# cert3d_rev2.net
KiCad netlist of a schematic drawn in EAGLE
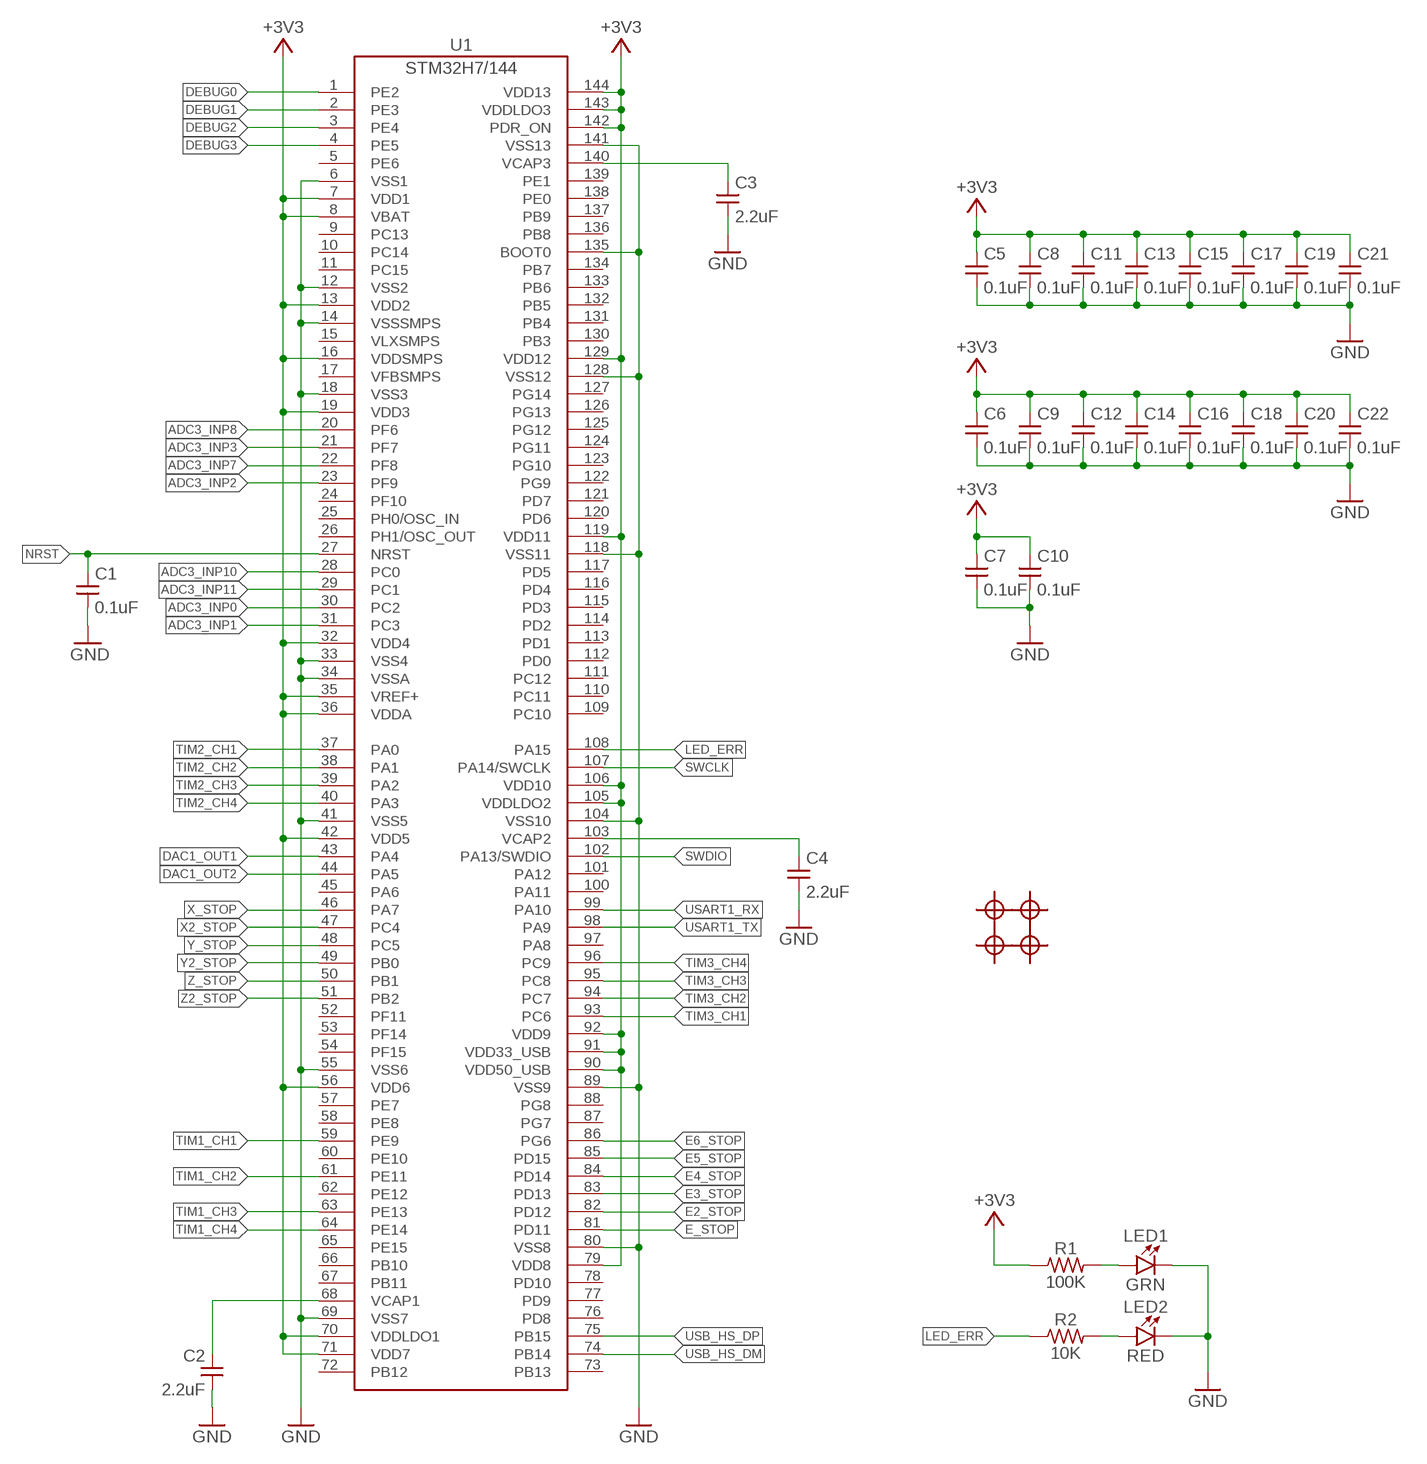
[diagram p0: schematic, sheet 1, part 1 of 2]
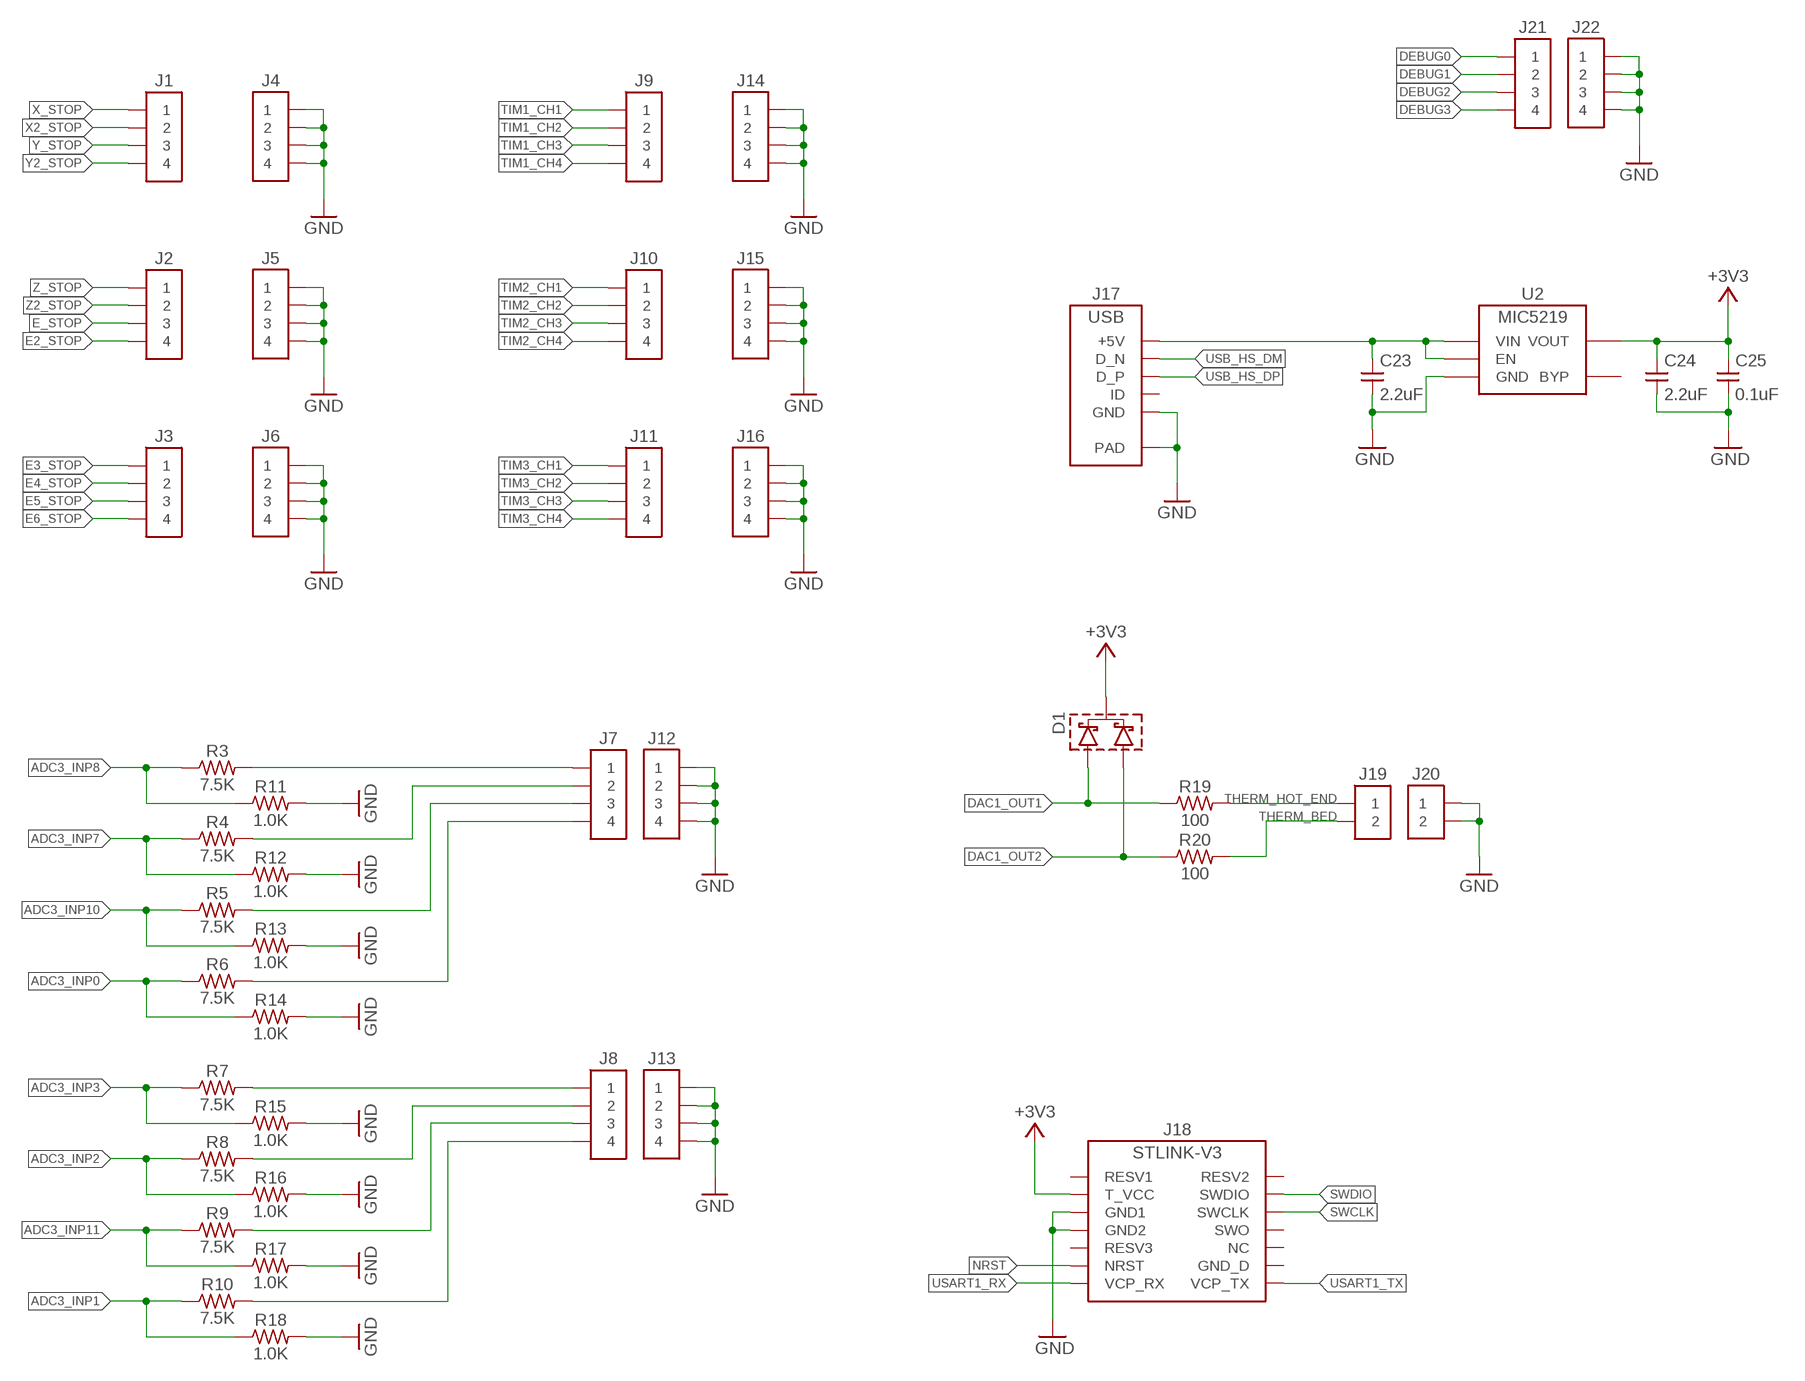
[diagram p1: schematic, sheet 1, part 2 of 2]

(export (version "E")
  (design (tool "Eeschema 10.0.6"))
  (components
    (comp (ref "C1")
      (value "0.1uF")
      (footprint "eagle-import:C0805-5MIL")
      (libsource (lib "eagle-import") (part "C_USC0805-5MIL"))
    )
    (comp (ref "C2")
      (value "2.2uF")
      (footprint "eagle-import:C0805-5MIL")
      (libsource (lib "eagle-import") (part "C_USC0805-5MIL"))
    )
    (comp (ref "C3")
      (value "2.2uF")
      (footprint "eagle-import:C0805-5MIL")
      (libsource (lib "eagle-import") (part "C_USC0805-5MIL"))
    )
    (comp (ref "C4")
      (value "2.2uF")
      (footprint "eagle-import:C0805-5MIL")
      (libsource (lib "eagle-import") (part "C_USC0805-5MIL"))
    )
    (comp (ref "C5")
      (value "0.1uF")
      (footprint "eagle-import:C0805-5MIL")
      (libsource (lib "eagle-import") (part "C_USC0805-5MIL"))
    )
    (comp (ref "C6")
      (value "0.1uF")
      (footprint "eagle-import:C0805-5MIL")
      (libsource (lib "eagle-import") (part "C_USC0805-5MIL"))
    )
    (comp (ref "C7")
      (value "0.1uF")
      (footprint "eagle-import:C0805-5MIL")
      (libsource (lib "eagle-import") (part "C_USC0805-5MIL"))
    )
    (comp (ref "C8")
      (value "0.1uF")
      (footprint "eagle-import:C0805-5MIL")
      (libsource (lib "eagle-import") (part "C_USC0805-5MIL"))
    )
    (comp (ref "C9")
      (value "0.1uF")
      (footprint "eagle-import:C0805-5MIL")
      (libsource (lib "eagle-import") (part "C_USC0805-5MIL"))
    )
    (comp (ref "C10")
      (value "0.1uF")
      (footprint "eagle-import:C0805-5MIL")
      (libsource (lib "eagle-import") (part "C_USC0805-5MIL"))
    )
    (comp (ref "C11")
      (value "0.1uF")
      (footprint "eagle-import:C0805-5MIL")
      (libsource (lib "eagle-import") (part "C_USC0805-5MIL"))
    )
    (comp (ref "C12")
      (value "0.1uF")
      (footprint "eagle-import:C0805-5MIL")
      (libsource (lib "eagle-import") (part "C_USC0805-5MIL"))
    )
    (comp (ref "C13")
      (value "0.1uF")
      (footprint "eagle-import:C0805-5MIL")
      (libsource (lib "eagle-import") (part "C_USC0805-5MIL"))
    )
    (comp (ref "C14")
      (value "0.1uF")
      (footprint "eagle-import:C0805-5MIL")
      (libsource (lib "eagle-import") (part "C_USC0805-5MIL"))
    )
    (comp (ref "C15")
      (value "0.1uF")
      (footprint "eagle-import:C0805-5MIL")
      (libsource (lib "eagle-import") (part "C_USC0805-5MIL"))
    )
    (comp (ref "C16")
      (value "0.1uF")
      (footprint "eagle-import:C0805-5MIL")
      (libsource (lib "eagle-import") (part "C_USC0805-5MIL"))
    )
    (comp (ref "C17")
      (value "0.1uF")
      (footprint "eagle-import:C0805-5MIL")
      (libsource (lib "eagle-import") (part "C_USC0805-5MIL"))
    )
    (comp (ref "C18")
      (value "0.1uF")
      (footprint "eagle-import:C0805-5MIL")
      (libsource (lib "eagle-import") (part "C_USC0805-5MIL"))
    )
    (comp (ref "C19")
      (value "0.1uF")
      (footprint "eagle-import:C0805-5MIL")
      (libsource (lib "eagle-import") (part "C_USC0805-5MIL"))
    )
    (comp (ref "C20")
      (value "0.1uF")
      (footprint "eagle-import:C0805-5MIL")
      (libsource (lib "eagle-import") (part "C_USC0805-5MIL"))
    )
    (comp (ref "C21")
      (value "0.1uF")
      (footprint "eagle-import:C0805-5MIL")
      (libsource (lib "eagle-import") (part "C_USC0805-5MIL"))
    )
    (comp (ref "C22")
      (value "0.1uF")
      (footprint "eagle-import:C0805-5MIL")
      (libsource (lib "eagle-import") (part "C_USC0805-5MIL"))
    )
    (comp (ref "C23")
      (value "2.2uF")
      (footprint "eagle-import:C0805-5MIL")
      (libsource (lib "eagle-import") (part "C_USC0805-5MIL"))
    )
    (comp (ref "C24")
      (value "2.2uF")
      (footprint "eagle-import:C0805-5MIL")
      (libsource (lib "eagle-import") (part "C_USC0805-5MIL"))
    )
    (comp (ref "C25")
      (value "0.1uF")
      (footprint "eagle-import:C0805-5MIL")
      (libsource (lib "eagle-import") (part "C_USC0805-5MIL"))
    )
    (comp (ref "D1")
      (value "SCHOTTKY_DUAL_CCBAT54C")
      (footprint "eagle-import:SOT23-3")
      (libsource (lib "eagle-import") (part "SCHOTTKY_DUAL_CCBAT54C"))
    )
    (comp (ref "FD1")
      (value "FIDUCIAL")
      (footprint "eagle-import:FID1MM")
      (libsource (lib "eagle-import") (part "FIDUCIAL"))
    )
    (comp (ref "FD2")
      (value "FIDUCIAL")
      (footprint "eagle-import:FID1MM")
      (libsource (lib "eagle-import") (part "FIDUCIAL"))
    )
    (comp (ref "FD3")
      (value "FIDUCIAL")
      (footprint "eagle-import:FID1MM")
      (libsource (lib "eagle-import") (part "FIDUCIAL"))
    )
    (comp (ref "FD4")
      (value "FIDUCIAL")
      (footprint "eagle-import:FID1MM")
      (libsource (lib "eagle-import") (part "FIDUCIAL"))
    )
    (comp (ref "J1")
      (value "CONN4TSW-S")
      (footprint "eagle-import:SAM-TSW-104-XX-X-S")
      (libsource (lib "eagle-import") (part "CONN4TSW-S"))
    )
    (comp (ref "J2")
      (value "CONN4TSW-S")
      (footprint "eagle-import:SAM-TSW-104-XX-X-S")
      (libsource (lib "eagle-import") (part "CONN4TSW-S"))
    )
    (comp (ref "J3")
      (value "CONN4TSW-S")
      (footprint "eagle-import:SAM-TSW-104-XX-X-S")
      (libsource (lib "eagle-import") (part "CONN4TSW-S"))
    )
    (comp (ref "J4")
      (value "CONN4TSW-S")
      (footprint "eagle-import:SAM-TSW-104-XX-X-S")
      (libsource (lib "eagle-import") (part "CONN4TSW-S"))
    )
    (comp (ref "J5")
      (value "CONN4TSW-S")
      (footprint "eagle-import:SAM-TSW-104-XX-X-S")
      (libsource (lib "eagle-import") (part "CONN4TSW-S"))
    )
    (comp (ref "J6")
      (value "CONN4TSW-S")
      (footprint "eagle-import:SAM-TSW-104-XX-X-S")
      (libsource (lib "eagle-import") (part "CONN4TSW-S"))
    )
    (comp (ref "J7")
      (value "CONN4TSW-S")
      (footprint "eagle-import:SAM-TSW-104-XX-X-S")
      (libsource (lib "eagle-import") (part "CONN4TSW-S"))
    )
    (comp (ref "J8")
      (value "CONN4TSW-S")
      (footprint "eagle-import:SAM-TSW-104-XX-X-S")
      (libsource (lib "eagle-import") (part "CONN4TSW-S"))
    )
    (comp (ref "J9")
      (value "CONN4TSW-S")
      (footprint "eagle-import:SAM-TSW-104-XX-X-S")
      (libsource (lib "eagle-import") (part "CONN4TSW-S"))
    )
    (comp (ref "J10")
      (value "CONN4TSW-S")
      (footprint "eagle-import:SAM-TSW-104-XX-X-S")
      (libsource (lib "eagle-import") (part "CONN4TSW-S"))
    )
    (comp (ref "J11")
      (value "CONN4TSW-S")
      (footprint "eagle-import:SAM-TSW-104-XX-X-S")
      (libsource (lib "eagle-import") (part "CONN4TSW-S"))
    )
    (comp (ref "J12")
      (value "CONN4TSW-S")
      (footprint "eagle-import:SAM-TSW-104-XX-X-S")
      (libsource (lib "eagle-import") (part "CONN4TSW-S"))
    )
    (comp (ref "J13")
      (value "CONN4TSW-S")
      (footprint "eagle-import:SAM-TSW-104-XX-X-S")
      (libsource (lib "eagle-import") (part "CONN4TSW-S"))
    )
    (comp (ref "J14")
      (value "CONN4TSW-S")
      (footprint "eagle-import:SAM-TSW-104-XX-X-S")
      (libsource (lib "eagle-import") (part "CONN4TSW-S"))
    )
    (comp (ref "J15")
      (value "CONN4TSW-S")
      (footprint "eagle-import:SAM-TSW-104-XX-X-S")
      (libsource (lib "eagle-import") (part "CONN4TSW-S"))
    )
    (comp (ref "J16")
      (value "CONN4TSW-S")
      (footprint "eagle-import:SAM-TSW-104-XX-X-S")
      (libsource (lib "eagle-import") (part "CONN4TSW-S"))
    )
    (comp (ref "J17")
      (value "USB-5PINTOPVIA")
      (footprint "eagle-import:HIR-ZX62R-B-5P-VIAS")
      (libsource (lib "eagle-import") (part "USB-5PINTOPVIA"))
    )
    (comp (ref "J18")
      (value "STLINK-V3/SWDCNC-3220")
      (footprint "eagle-import:CNC-3220-14-0100-00")
      (libsource (lib "eagle-import") (part "STLINK-V3/SWDCNC-3220"))
    )
    (comp (ref "J19")
      (value "CONN2TSW-S")
      (footprint "eagle-import:SAM-TSW-102-XX-X-S")
      (libsource (lib "eagle-import") (part "CONN2TSW-S"))
    )
    (comp (ref "J20")
      (value "CONN2TSW-S")
      (footprint "eagle-import:SAM-TSW-102-XX-X-S")
      (libsource (lib "eagle-import") (part "CONN2TSW-S"))
    )
    (comp (ref "J21")
      (value "CONN4TSW-S")
      (footprint "eagle-import:SAM-TSW-104-XX-X-S")
      (libsource (lib "eagle-import") (part "CONN4TSW-S"))
    )
    (comp (ref "J22")
      (value "CONN4TSW-S")
      (footprint "eagle-import:SAM-TSW-104-XX-X-S")
      (libsource (lib "eagle-import") (part "CONN4TSW-S"))
    )
    (comp (ref "LED1")
      (value "GRN")
      (footprint "eagle-import:CHIPLED0805-SMALL")
      (libsource (lib "eagle-import") (part "LEDCHIPLED0805-SMALL"))
    )
    (comp (ref "LED2")
      (value "RED")
      (footprint "eagle-import:CHIPLED0805-SMALL")
      (libsource (lib "eagle-import") (part "LEDCHIPLED0805-SMALL"))
    )
    (comp (ref "R1")
      (value "100K")
      (footprint "eagle-import:RES0805R-5MIL")
      (libsource (lib "eagle-import") (part "R_USRES0805-5MIL"))
    )
    (comp (ref "R2")
      (value "10K")
      (footprint "eagle-import:RES0805R-5MIL")
      (libsource (lib "eagle-import") (part "R_USRES0805-5MIL"))
    )
    (comp (ref "R3")
      (value "7.5K")
      (footprint "eagle-import:RES0805R-5MIL")
      (libsource (lib "eagle-import") (part "R_USRES0805-5MIL"))
    )
    (comp (ref "R4")
      (value "7.5K")
      (footprint "eagle-import:RES0805R-5MIL")
      (libsource (lib "eagle-import") (part "R_USRES0805-5MIL"))
    )
    (comp (ref "R5")
      (value "7.5K")
      (footprint "eagle-import:RES0805R-5MIL")
      (libsource (lib "eagle-import") (part "R_USRES0805-5MIL"))
    )
    (comp (ref "R6")
      (value "7.5K")
      (footprint "eagle-import:RES0805R-5MIL")
      (libsource (lib "eagle-import") (part "R_USRES0805-5MIL"))
    )
    (comp (ref "R7")
      (value "7.5K")
      (footprint "eagle-import:RES0805R-5MIL")
      (libsource (lib "eagle-import") (part "R_USRES0805-5MIL"))
    )
    (comp (ref "R8")
      (value "7.5K")
      (footprint "eagle-import:RES0805R-5MIL")
      (libsource (lib "eagle-import") (part "R_USRES0805-5MIL"))
    )
    (comp (ref "R9")
      (value "7.5K")
      (footprint "eagle-import:RES0805R-5MIL")
      (libsource (lib "eagle-import") (part "R_USRES0805-5MIL"))
    )
    (comp (ref "R10")
      (value "7.5K")
      (footprint "eagle-import:RES0805R-5MIL")
      (libsource (lib "eagle-import") (part "R_USRES0805-5MIL"))
    )
    (comp (ref "R11")
      (value "1.0K")
      (footprint "eagle-import:RES0805R-5MIL")
      (libsource (lib "eagle-import") (part "R_USRES0805-5MIL"))
    )
    (comp (ref "R12")
      (value "1.0K")
      (footprint "eagle-import:RES0805R-5MIL")
      (libsource (lib "eagle-import") (part "R_USRES0805-5MIL"))
    )
    (comp (ref "R13")
      (value "1.0K")
      (footprint "eagle-import:RES0805R-5MIL")
      (libsource (lib "eagle-import") (part "R_USRES0805-5MIL"))
    )
    (comp (ref "R14")
      (value "1.0K")
      (footprint "eagle-import:RES0805R-5MIL")
      (libsource (lib "eagle-import") (part "R_USRES0805-5MIL"))
    )
    (comp (ref "R15")
      (value "1.0K")
      (footprint "eagle-import:RES0805R-5MIL")
      (libsource (lib "eagle-import") (part "R_USRES0805-5MIL"))
    )
    (comp (ref "R16")
      (value "1.0K")
      (footprint "eagle-import:RES0805R-5MIL")
      (libsource (lib "eagle-import") (part "R_USRES0805-5MIL"))
    )
    (comp (ref "R17")
      (value "1.0K")
      (footprint "eagle-import:RES0805R-5MIL")
      (libsource (lib "eagle-import") (part "R_USRES0805-5MIL"))
    )
    (comp (ref "R18")
      (value "1.0K")
      (footprint "eagle-import:RES0805R-5MIL")
      (libsource (lib "eagle-import") (part "R_USRES0805-5MIL"))
    )
    (comp (ref "R19")
      (value "100")
      (footprint "eagle-import:RES0805R-5MIL")
      (libsource (lib "eagle-import") (part "R_USRES0805-5MIL"))
    )
    (comp (ref "R20")
      (value "100")
      (footprint "eagle-import:RES0805R-5MIL")
      (libsource (lib "eagle-import") (part "R_USRES0805-5MIL"))
    )
    (comp (ref "U1")
      (value "STM32H745-144")
      (footprint "eagle-import:LQFP144-20X20MM")
      (libsource (lib "eagle-import") (part "STM32H745-144"))
    )
    (comp (ref "U2")
      (value "MIC5219")
      (footprint "eagle-import:SOT23-5")
      (libsource (lib "eagle-import") (part "MIC5219"))
    )
  )
  (nets
    (net (code "1") (name "+3V3") (class "Default")
      (node (ref "C10") (pin "1") (pinfunction "1_1") (pintype "passive"))
      (node (ref "C11") (pin "1") (pinfunction "1_1") (pintype "passive"))
      (node (ref "C12") (pin "1") (pinfunction "1_1") (pintype "passive"))
      (node (ref "C13") (pin "1") (pinfunction "1_1") (pintype "passive"))
      (node (ref "C14") (pin "1") (pinfunction "1_1") (pintype "passive"))
      (node (ref "C15") (pin "1") (pinfunction "1_1") (pintype "passive"))
      (node (ref "C16") (pin "1") (pinfunction "1_1") (pintype "passive"))
      (node (ref "C17") (pin "1") (pinfunction "1_1") (pintype "passive"))
      (node (ref "C18") (pin "1") (pinfunction "1_1") (pintype "passive"))
      (node (ref "C19") (pin "1") (pinfunction "1_1") (pintype "passive"))
      (node (ref "C20") (pin "1") (pinfunction "1_1") (pintype "passive"))
      (node (ref "C21") (pin "1") (pinfunction "1_1") (pintype "passive"))
      (node (ref "C22") (pin "1") (pinfunction "1_1") (pintype "passive"))
      (node (ref "C24") (pin "1") (pinfunction "1_1") (pintype "passive"))
      (node (ref "C25") (pin "1") (pinfunction "1_1") (pintype "passive"))
      (node (ref "C5") (pin "1") (pinfunction "1_1") (pintype "passive"))
      (node (ref "C6") (pin "1") (pinfunction "1_1") (pintype "passive"))
      (node (ref "C7") (pin "1") (pinfunction "1_1") (pintype "passive"))
      (node (ref "C8") (pin "1") (pinfunction "1_1") (pintype "passive"))
      (node (ref "C9") (pin "1") (pinfunction "1_1") (pintype "passive"))
      (node (ref "D1") (pin "3") (pinfunction "C_3") (pintype "passive"))
      (node (ref "J18") (pin "3") (pinfunction "T_VCC_3") (pintype "input"))
      (node (ref "R1") (pin "1") (pinfunction "1_1") (pintype "passive"))
      (node (ref "U1") (pin "105") (pinfunction "VDDLDO2_105") (pintype "bidirectional"))
      (node (ref "U1") (pin "106") (pinfunction "VDD10_106") (pintype "bidirectional"))
      (node (ref "U1") (pin "119") (pinfunction "VDD11_119") (pintype "bidirectional"))
      (node (ref "U1") (pin "129") (pinfunction "VDD12_129") (pintype "bidirectional"))
      (node (ref "U1") (pin "13") (pinfunction "VDD2_13") (pintype "bidirectional"))
      (node (ref "U1") (pin "142") (pinfunction "PDR_ON_142") (pintype "bidirectional"))
      (node (ref "U1") (pin "143") (pinfunction "VDDLDO3_143") (pintype "bidirectional"))
      (node (ref "U1") (pin "144") (pinfunction "VDD13_144") (pintype "bidirectional"))
      (node (ref "U1") (pin "16") (pinfunction "VDDSMPS_16") (pintype "bidirectional"))
      (node (ref "U1") (pin "19") (pinfunction "VDD3_19") (pintype "bidirectional"))
      (node (ref "U1") (pin "32") (pinfunction "VDD4_32") (pintype "bidirectional"))
      (node (ref "U1") (pin "35") (pinfunction "VREF+_35") (pintype "bidirectional"))
      (node (ref "U1") (pin "36") (pinfunction "VDDA_36") (pintype "bidirectional"))
      (node (ref "U1") (pin "42") (pinfunction "VDD5_42") (pintype "bidirectional"))
      (node (ref "U1") (pin "56") (pinfunction "VDD6_56") (pintype "bidirectional"))
      (node (ref "U1") (pin "7") (pinfunction "VDD1_7") (pintype "bidirectional"))
      (node (ref "U1") (pin "70") (pinfunction "VDDLDO1_70") (pintype "bidirectional"))
      (node (ref "U1") (pin "71") (pinfunction "VDD7_71") (pintype "bidirectional"))
      (node (ref "U1") (pin "79") (pinfunction "VDD8_79") (pintype "bidirectional"))
      (node (ref "U1") (pin "8") (pinfunction "VBAT_8") (pintype "bidirectional"))
      (node (ref "U1") (pin "90") (pinfunction "VDD50_USB_90") (pintype "bidirectional"))
      (node (ref "U1") (pin "91") (pinfunction "VDD33_USB_91") (pintype "bidirectional"))
      (node (ref "U1") (pin "92") (pinfunction "VDD9_92") (pintype "bidirectional"))
      (node (ref "U2") (pin "5") (pinfunction "VOUT_5") (pintype "bidirectional"))
    )
    (net (code "2") (name "/THERM_BED") (class "Default")
      (node (ref "J19") (pin "2") (pinfunction "2_2") (pintype "passive"))
      (node (ref "R20") (pin "2") (pinfunction "2_2") (pintype "passive"))
    )
    (net (code "3") (name "/THERM_HOT_END") (class "Default")
      (node (ref "J19") (pin "1") (pinfunction "1_1") (pintype "passive"))
      (node (ref "R19") (pin "2") (pinfunction "2_2") (pintype "passive"))
    )
    (net (code "4") (name "ADC3_INP0") (class "Default")
      (node (ref "R14") (pin "1") (pinfunction "1_1") (pintype "passive"))
      (node (ref "R6") (pin "1") (pinfunction "1_1") (pintype "passive"))
      (node (ref "U1") (pin "30") (pinfunction "PC2_30") (pintype "bidirectional"))
    )
    (net (code "5") (name "ADC3_INP1") (class "Default")
      (node (ref "R10") (pin "1") (pinfunction "1_1") (pintype "passive"))
      (node (ref "R18") (pin "1") (pinfunction "1_1") (pintype "passive"))
      (node (ref "U1") (pin "31") (pinfunction "PC3_31") (pintype "bidirectional"))
    )
    (net (code "6") (name "ADC3_INP2") (class "Default")
      (node (ref "R16") (pin "1") (pinfunction "1_1") (pintype "passive"))
      (node (ref "R8") (pin "1") (pinfunction "1_1") (pintype "passive"))
      (node (ref "U1") (pin "23") (pinfunction "PF9_23") (pintype "bidirectional"))
    )
    (net (code "7") (name "ADC3_INP3") (class "Default")
      (node (ref "R15") (pin "1") (pinfunction "1_1") (pintype "passive"))
      (node (ref "R7") (pin "1") (pinfunction "1_1") (pintype "passive"))
      (node (ref "U1") (pin "21") (pinfunction "PF7_21") (pintype "bidirectional"))
    )
    (net (code "8") (name "ADC3_INP7") (class "Default")
      (node (ref "R12") (pin "1") (pinfunction "1_1") (pintype "passive"))
      (node (ref "R4") (pin "1") (pinfunction "1_1") (pintype "passive"))
      (node (ref "U1") (pin "22") (pinfunction "PF8_22") (pintype "bidirectional"))
    )
    (net (code "9") (name "ADC3_INP8") (class "Default")
      (node (ref "R11") (pin "1") (pinfunction "1_1") (pintype "passive"))
      (node (ref "R3") (pin "1") (pinfunction "1_1") (pintype "passive"))
      (node (ref "U1") (pin "20") (pinfunction "PF6_20") (pintype "bidirectional"))
    )
    (net (code "10") (name "ADC3_INP10") (class "Default")
      (node (ref "R13") (pin "1") (pinfunction "1_1") (pintype "passive"))
      (node (ref "R5") (pin "1") (pinfunction "1_1") (pintype "passive"))
      (node (ref "U1") (pin "28") (pinfunction "PC0_28") (pintype "bidirectional"))
    )
    (net (code "11") (name "ADC3_INP11") (class "Default")
      (node (ref "R17") (pin "1") (pinfunction "1_1") (pintype "passive"))
      (node (ref "R9") (pin "1") (pinfunction "1_1") (pintype "passive"))
      (node (ref "U1") (pin "29") (pinfunction "PC1_29") (pintype "bidirectional"))
    )
    (net (code "12") (name "DAC1_OUT1") (class "Default")
      (node (ref "D1") (pin "1") (pinfunction "A1_1") (pintype "passive"))
      (node (ref "R19") (pin "1") (pinfunction "1_1") (pintype "passive"))
      (node (ref "U1") (pin "43") (pinfunction "PA4_43") (pintype "bidirectional"))
    )
    (net (code "13") (name "DAC1_OUT2") (class "Default")
      (node (ref "D1") (pin "2") (pinfunction "A2_2") (pintype "passive"))
      (node (ref "R20") (pin "1") (pinfunction "1_1") (pintype "passive"))
      (node (ref "U1") (pin "44") (pinfunction "PA5_44") (pintype "bidirectional"))
    )
    (net (code "14") (name "DEBUG0") (class "Default")
      (node (ref "J21") (pin "1") (pinfunction "1_1") (pintype "passive"))
      (node (ref "U1") (pin "1") (pinfunction "PE2_1") (pintype "bidirectional"))
    )
    (net (code "15") (name "DEBUG1") (class "Default")
      (node (ref "J21") (pin "2") (pinfunction "2_2") (pintype "passive"))
      (node (ref "U1") (pin "2") (pinfunction "PE3_2") (pintype "bidirectional"))
    )
    (net (code "16") (name "DEBUG2") (class "Default")
      (node (ref "J21") (pin "3") (pinfunction "3_3") (pintype "passive"))
      (node (ref "U1") (pin "3") (pinfunction "PE4_3") (pintype "bidirectional"))
    )
    (net (code "17") (name "DEBUG3") (class "Default")
      (node (ref "J21") (pin "4") (pinfunction "4_4") (pintype "passive"))
      (node (ref "U1") (pin "4") (pinfunction "PE5_4") (pintype "bidirectional"))
    )
    (net (code "18") (name "E2_STOP") (class "Default")
      (node (ref "J2") (pin "4") (pinfunction "4_4") (pintype "passive"))
      (node (ref "U1") (pin "82") (pinfunction "PD12_82") (pintype "bidirectional"))
    )
    (net (code "19") (name "E3_STOP") (class "Default")
      (node (ref "J3") (pin "1") (pinfunction "1_1") (pintype "passive"))
      (node (ref "U1") (pin "83") (pinfunction "PD13_83") (pintype "bidirectional"))
    )
    (net (code "20") (name "E4_STOP") (class "Default")
      (node (ref "J3") (pin "2") (pinfunction "2_2") (pintype "passive"))
      (node (ref "U1") (pin "84") (pinfunction "PD14_84") (pintype "bidirectional"))
    )
    (net (code "21") (name "E5_STOP") (class "Default")
      (node (ref "J3") (pin "3") (pinfunction "3_3") (pintype "passive"))
      (node (ref "U1") (pin "85") (pinfunction "PD15_85") (pintype "bidirectional"))
    )
    (net (code "22") (name "E6_STOP") (class "Default")
      (node (ref "J3") (pin "4") (pinfunction "4_4") (pintype "passive"))
      (node (ref "U1") (pin "86") (pinfunction "PG6_86") (pintype "bidirectional"))
    )
    (net (code "23") (name "E_STOP") (class "Default")
      (node (ref "J2") (pin "3") (pinfunction "3_3") (pintype "passive"))
      (node (ref "U1") (pin "81") (pinfunction "PD11_81") (pintype "bidirectional"))
    )
    (net (code "24") (name "GND") (class "Default")
      (node (ref "C1") (pin "2") (pinfunction "2_2") (pintype "passive"))
      (node (ref "C10") (pin "2") (pinfunction "2_2") (pintype "passive"))
      (node (ref "C11") (pin "2") (pinfunction "2_2") (pintype "passive"))
      (node (ref "C12") (pin "2") (pinfunction "2_2") (pintype "passive"))
      (node (ref "C13") (pin "2") (pinfunction "2_2") (pintype "passive"))
      (node (ref "C14") (pin "2") (pinfunction "2_2") (pintype "passive"))
      (node (ref "C15") (pin "2") (pinfunction "2_2") (pintype "passive"))
      (node (ref "C16") (pin "2") (pinfunction "2_2") (pintype "passive"))
      (node (ref "C17") (pin "2") (pinfunction "2_2") (pintype "passive"))
      (node (ref "C18") (pin "2") (pinfunction "2_2") (pintype "passive"))
      (node (ref "C19") (pin "2") (pinfunction "2_2") (pintype "passive"))
      (node (ref "C2") (pin "2") (pinfunction "2_2") (pintype "passive"))
      (node (ref "C20") (pin "2") (pinfunction "2_2") (pintype "passive"))
      (node (ref "C21") (pin "2") (pinfunction "2_2") (pintype "passive"))
      (node (ref "C22") (pin "2") (pinfunction "2_2") (pintype "passive"))
      (node (ref "C23") (pin "2") (pinfunction "2_2") (pintype "passive"))
      (node (ref "C24") (pin "2") (pinfunction "2_2") (pintype "passive"))
      (node (ref "C25") (pin "2") (pinfunction "2_2") (pintype "passive"))
      (node (ref "C3") (pin "2") (pinfunction "2_2") (pintype "passive"))
      (node (ref "C4") (pin "2") (pinfunction "2_2") (pintype "passive"))
      (node (ref "C5") (pin "2") (pinfunction "2_2") (pintype "passive"))
      (node (ref "C6") (pin "2") (pinfunction "2_2") (pintype "passive"))
      (node (ref "C7") (pin "2") (pinfunction "2_2") (pintype "passive"))
      (node (ref "C8") (pin "2") (pinfunction "2_2") (pintype "passive"))
      (node (ref "C9") (pin "2") (pinfunction "2_2") (pintype "passive"))
      (node (ref "J12") (pin "1") (pinfunction "1_1") (pintype "passive"))
      (node (ref "J12") (pin "2") (pinfunction "2_2") (pintype "passive"))
      (node (ref "J12") (pin "3") (pinfunction "3_3") (pintype "passive"))
      (node (ref "J12") (pin "4") (pinfunction "4_4") (pintype "passive"))
      (node (ref "J13") (pin "1") (pinfunction "1_1") (pintype "passive"))
      (node (ref "J13") (pin "2") (pinfunction "2_2") (pintype "passive"))
      (node (ref "J13") (pin "3") (pinfunction "3_3") (pintype "passive"))
      (node (ref "J13") (pin "4") (pinfunction "4_4") (pintype "passive"))
      (node (ref "J14") (pin "1") (pinfunction "1_1") (pintype "passive"))
      (node (ref "J14") (pin "2") (pinfunction "2_2") (pintype "passive"))
      (node (ref "J14") (pin "3") (pinfunction "3_3") (pintype "passive"))
      (node (ref "J14") (pin "4") (pinfunction "4_4") (pintype "passive"))
      (node (ref "J15") (pin "1") (pinfunction "1_1") (pintype "passive"))
      (node (ref "J15") (pin "2") (pinfunction "2_2") (pintype "passive"))
      (node (ref "J15") (pin "3") (pinfunction "3_3") (pintype "passive"))
      (node (ref "J15") (pin "4") (pinfunction "4_4") (pintype "passive"))
      (node (ref "J16") (pin "1") (pinfunction "1_1") (pintype "passive"))
      (node (ref "J16") (pin "2") (pinfunction "2_2") (pintype "passive"))
      (node (ref "J16") (pin "3") (pinfunction "3_3") (pintype "passive"))
      (node (ref "J16") (pin "4") (pinfunction "4_4") (pintype "passive"))
      (node (ref "J17") (pin "5") (pinfunction "GND_5") (pintype "bidirectional"))
      (node (ref "J17") (pin "PAD@1") (pinfunction "PAD_PAD@1") (pintype "bidirectional"))
      (node (ref "J17") (pin "PAD@10") (pinfunction "PAD_PAD@10") (pintype "bidirectional"))
      (node (ref "J17") (pin "PAD@11") (pinfunction "PAD_PAD@11") (pintype "bidirectional"))
      (node (ref "J17") (pin "PAD@12") (pinfunction "PAD_PAD@12") (pintype "bidirectional"))
      (node (ref "J17") (pin "PAD@2") (pinfunction "PAD_PAD@2") (pintype "bidirectional"))
      (node (ref "J17") (pin "PAD@3") (pinfunction "PAD_PAD@3") (pintype "bidirectional"))
      (node (ref "J17") (pin "PAD@4") (pinfunction "PAD_PAD@4") (pintype "bidirectional"))
      (node (ref "J17") (pin "PAD@5") (pinfunction "PAD_PAD@5") (pintype "bidirectional"))
      (node (ref "J17") (pin "PAD@6") (pinfunction "PAD_PAD@6") (pintype "bidirectional"))
      (node (ref "J17") (pin "PAD@7") (pinfunction "PAD_PAD@7") (pintype "bidirectional"))
      (node (ref "J17") (pin "PAD@8") (pinfunction "PAD_PAD@8") (pintype "bidirectional"))
      (node (ref "J17") (pin "PAD@9") (pinfunction "PAD_PAD@9") (pintype "bidirectional"))
      (node (ref "J18") (pin "5") (pinfunction "GND1_5") (pintype "passive"))
      (node (ref "J18") (pin "7") (pinfunction "GND2_7") (pintype "passive"))
      (node (ref "J20") (pin "1") (pinfunction "1_1") (pintype "passive"))
      (node (ref "J20") (pin "2") (pinfunction "2_2") (pintype "passive"))
      (node (ref "J22") (pin "1") (pinfunction "1_1") (pintype "passive"))
      (node (ref "J22") (pin "2") (pinfunction "2_2") (pintype "passive"))
      (node (ref "J22") (pin "3") (pinfunction "3_3") (pintype "passive"))
      (node (ref "J22") (pin "4") (pinfunction "4_4") (pintype "passive"))
      (node (ref "J4") (pin "1") (pinfunction "1_1") (pintype "passive"))
      (node (ref "J4") (pin "2") (pinfunction "2_2") (pintype "passive"))
      (node (ref "J4") (pin "3") (pinfunction "3_3") (pintype "passive"))
      (node (ref "J4") (pin "4") (pinfunction "4_4") (pintype "passive"))
      (node (ref "J5") (pin "1") (pinfunction "1_1") (pintype "passive"))
      (node (ref "J5") (pin "2") (pinfunction "2_2") (pintype "passive"))
      (node (ref "J5") (pin "3") (pinfunction "3_3") (pintype "passive"))
      (node (ref "J5") (pin "4") (pinfunction "4_4") (pintype "passive"))
      (node (ref "J6") (pin "1") (pinfunction "1_1") (pintype "passive"))
      (node (ref "J6") (pin "2") (pinfunction "2_2") (pintype "passive"))
      (node (ref "J6") (pin "3") (pinfunction "3_3") (pintype "passive"))
      (node (ref "J6") (pin "4") (pinfunction "4_4") (pintype "passive"))
      (node (ref "LED1") (pin "C") (pinfunction "C_C") (pintype "passive"))
      (node (ref "LED2") (pin "C") (pinfunction "C_C") (pintype "passive"))
      (node (ref "R11") (pin "2") (pinfunction "2_2") (pintype "passive"))
      (node (ref "R12") (pin "2") (pinfunction "2_2") (pintype "passive"))
      (node (ref "R13") (pin "2") (pinfunction "2_2") (pintype "passive"))
      (node (ref "R14") (pin "2") (pinfunction "2_2") (pintype "passive"))
      (node (ref "R15") (pin "2") (pinfunction "2_2") (pintype "passive"))
      (node (ref "R16") (pin "2") (pinfunction "2_2") (pintype "passive"))
      (node (ref "R17") (pin "2") (pinfunction "2_2") (pintype "passive"))
      (node (ref "R18") (pin "2") (pinfunction "2_2") (pintype "passive"))
      (node (ref "U1") (pin "104") (pinfunction "VSS10_104") (pintype "bidirectional"))
      (node (ref "U1") (pin "118") (pinfunction "VSS11_118") (pintype "bidirectional"))
      (node (ref "U1") (pin "12") (pinfunction "VSS2_12") (pintype "bidirectional"))
      (node (ref "U1") (pin "128") (pinfunction "VSS12_128") (pintype "bidirectional"))
      (node (ref "U1") (pin "135") (pinfunction "BOOT0_135") (pintype "bidirectional"))
      (node (ref "U1") (pin "14") (pinfunction "VSSSMPS_14") (pintype "bidirectional"))
      (node (ref "U1") (pin "141") (pinfunction "VSS13_141") (pintype "bidirectional"))
      (node (ref "U1") (pin "18") (pinfunction "VSS3_18") (pintype "bidirectional"))
      (node (ref "U1") (pin "33") (pinfunction "VSS4_33") (pintype "bidirectional"))
      (node (ref "U1") (pin "34") (pinfunction "VSSA_34") (pintype "bidirectional"))
      (node (ref "U1") (pin "41") (pinfunction "VSS5_41") (pintype "bidirectional"))
      (node (ref "U1") (pin "55") (pinfunction "VSS6_55") (pintype "bidirectional"))
      (node (ref "U1") (pin "6") (pinfunction "VSS1_6") (pintype "bidirectional"))
      (node (ref "U1") (pin "69") (pinfunction "VSS7_69") (pintype "bidirectional"))
      (node (ref "U1") (pin "80") (pinfunction "VSS8_80") (pintype "bidirectional"))
      (node (ref "U1") (pin "89") (pinfunction "VSS9_89") (pintype "bidirectional"))
      (node (ref "U2") (pin "2") (pinfunction "GND_2") (pintype "bidirectional"))
    )
    (net (code "25") (name "LED_ERR") (class "Default")
      (node (ref "R2") (pin "1") (pinfunction "1_1") (pintype "passive"))
      (node (ref "U1") (pin "108") (pinfunction "PA15_108") (pintype "bidirectional"))
    )
    (net (code "26") (name "NRST") (class "Default")
      (node (ref "C1") (pin "1") (pinfunction "1_1") (pintype "passive"))
      (node (ref "J18") (pin "11") (pinfunction "NRST_11") (pintype "passive"))
      (node (ref "U1") (pin "27") (pinfunction "NRST_27") (pintype "bidirectional"))
    )
    (net (code "27") (name "Net-(J7-Pad1)") (class "Default")
      (node (ref "J7") (pin "1") (pinfunction "1_1") (pintype "passive"))
      (node (ref "R3") (pin "2") (pinfunction "2_2") (pintype "passive"))
    )
    (net (code "28") (name "Net-(J7-Pad2)") (class "Default")
      (node (ref "J7") (pin "2") (pinfunction "2_2") (pintype "passive"))
      (node (ref "R4") (pin "2") (pinfunction "2_2") (pintype "passive"))
    )
    (net (code "29") (name "Net-(J7-Pad3)") (class "Default")
      (node (ref "J7") (pin "3") (pinfunction "3_3") (pintype "passive"))
      (node (ref "R5") (pin "2") (pinfunction "2_2") (pintype "passive"))
    )
    (net (code "30") (name "Net-(J7-Pad4)") (class "Default")
      (node (ref "J7") (pin "4") (pinfunction "4_4") (pintype "passive"))
      (node (ref "R6") (pin "2") (pinfunction "2_2") (pintype "passive"))
    )
    (net (code "31") (name "Net-(J8-Pad1)") (class "Default")
      (node (ref "J8") (pin "1") (pinfunction "1_1") (pintype "passive"))
      (node (ref "R7") (pin "2") (pinfunction "2_2") (pintype "passive"))
    )
    (net (code "32") (name "Net-(J8-Pad2)") (class "Default")
      (node (ref "J8") (pin "2") (pinfunction "2_2") (pintype "passive"))
      (node (ref "R8") (pin "2") (pinfunction "2_2") (pintype "passive"))
    )
    (net (code "33") (name "Net-(J8-Pad3)") (class "Default")
      (node (ref "J8") (pin "3") (pinfunction "3_3") (pintype "passive"))
      (node (ref "R9") (pin "2") (pinfunction "2_2") (pintype "passive"))
    )
    (net (code "34") (name "Net-(J8-Pad4)") (class "Default")
      (node (ref "J8") (pin "4") (pinfunction "4_4") (pintype "passive"))
      (node (ref "R10") (pin "2") (pinfunction "2_2") (pintype "passive"))
    )
    (net (code "35") (name "Net-(J17-+5V)") (class "Default")
      (node (ref "C23") (pin "1") (pinfunction "1_1") (pintype "passive"))
      (node (ref "J17") (pin "1") (pinfunction "+5V_1") (pintype "bidirectional"))
      (node (ref "U2") (pin "1") (pinfunction "VIN_1") (pintype "bidirectional"))
      (node (ref "U2") (pin "3") (pinfunction "EN_3") (pintype "bidirectional"))
    )
    (net (code "36") (name "Net-(LED1-PadA)") (class "Default")
      (node (ref "LED1") (pin "A") (pinfunction "A_A") (pintype "passive"))
      (node (ref "R1") (pin "2") (pinfunction "2_2") (pintype "passive"))
    )
    (net (code "37") (name "Net-(LED2-PadA)") (class "Default")
      (node (ref "LED2") (pin "A") (pinfunction "A_A") (pintype "passive"))
      (node (ref "R2") (pin "2") (pinfunction "2_2") (pintype "passive"))
    )
    (net (code "38") (name "Net-(U1-VCAP1)") (class "Default")
      (node (ref "C2") (pin "1") (pinfunction "1_1") (pintype "passive"))
      (node (ref "U1") (pin "68") (pinfunction "VCAP1_68") (pintype "bidirectional"))
    )
    (net (code "39") (name "Net-(U1-VCAP2)") (class "Default")
      (node (ref "C4") (pin "1") (pinfunction "1_1") (pintype "passive"))
      (node (ref "U1") (pin "103") (pinfunction "VCAP2_103") (pintype "bidirectional"))
    )
    (net (code "40") (name "Net-(U1-VCAP3)") (class "Default")
      (node (ref "C3") (pin "1") (pinfunction "1_1") (pintype "passive"))
      (node (ref "U1") (pin "140") (pinfunction "VCAP3_140") (pintype "bidirectional"))
    )
    (net (code "41") (name "SWCLK") (class "Default")
      (node (ref "J18") (pin "6") (pinfunction "SWCLK_6") (pintype "passive"))
      (node (ref "U1") (pin "107") (pinfunction "PA14/SWCLK_107") (pintype "bidirectional"))
    )
    (net (code "42") (name "SWDIO") (class "Default")
      (node (ref "J18") (pin "4") (pinfunction "SWDIO_4") (pintype "passive"))
      (node (ref "U1") (pin "102") (pinfunction "PA13/SWDIO_102") (pintype "bidirectional"))
    )
    (net (code "43") (name "TIM1_CH1") (class "Default")
      (node (ref "J9") (pin "1") (pinfunction "1_1") (pintype "passive"))
      (node (ref "U1") (pin "59") (pinfunction "PE9_59") (pintype "bidirectional"))
    )
    (net (code "44") (name "TIM1_CH2") (class "Default")
      (node (ref "J9") (pin "2") (pinfunction "2_2") (pintype "passive"))
      (node (ref "U1") (pin "61") (pinfunction "PE11_61") (pintype "bidirectional"))
    )
    (net (code "45") (name "TIM1_CH3") (class "Default")
      (node (ref "J9") (pin "3") (pinfunction "3_3") (pintype "passive"))
      (node (ref "U1") (pin "63") (pinfunction "PE13_63") (pintype "bidirectional"))
    )
    (net (code "46") (name "TIM1_CH4") (class "Default")
      (node (ref "J9") (pin "4") (pinfunction "4_4") (pintype "passive"))
      (node (ref "U1") (pin "64") (pinfunction "PE14_64") (pintype "bidirectional"))
    )
    (net (code "47") (name "TIM2_CH1") (class "Default")
      (node (ref "J10") (pin "1") (pinfunction "1_1") (pintype "passive"))
      (node (ref "U1") (pin "37") (pinfunction "PA0_37") (pintype "bidirectional"))
    )
    (net (code "48") (name "TIM2_CH2") (class "Default")
      (node (ref "J10") (pin "2") (pinfunction "2_2") (pintype "passive"))
      (node (ref "U1") (pin "38") (pinfunction "PA1_38") (pintype "bidirectional"))
    )
    (net (code "49") (name "TIM2_CH3") (class "Default")
      (node (ref "J10") (pin "3") (pinfunction "3_3") (pintype "passive"))
      (node (ref "U1") (pin "39") (pinfunction "PA2_39") (pintype "bidirectional"))
    )
    (net (code "50") (name "TIM2_CH4") (class "Default")
      (node (ref "J10") (pin "4") (pinfunction "4_4") (pintype "passive"))
      (node (ref "U1") (pin "40") (pinfunction "PA3_40") (pintype "bidirectional"))
    )
    (net (code "51") (name "TIM3_CH1") (class "Default")
      (node (ref "J11") (pin "1") (pinfunction "1_1") (pintype "passive"))
      (node (ref "U1") (pin "93") (pinfunction "PC6_93") (pintype "bidirectional"))
    )
    (net (code "52") (name "TIM3_CH2") (class "Default")
      (node (ref "J11") (pin "2") (pinfunction "2_2") (pintype "passive"))
      (node (ref "U1") (pin "94") (pinfunction "PC7_94") (pintype "bidirectional"))
    )
    (net (code "53") (name "TIM3_CH3") (class "Default")
      (node (ref "J11") (pin "3") (pinfunction "3_3") (pintype "passive"))
      (node (ref "U1") (pin "95") (pinfunction "PC8_95") (pintype "bidirectional"))
    )
    (net (code "54") (name "TIM3_CH4") (class "Default")
      (node (ref "J11") (pin "4") (pinfunction "4_4") (pintype "passive"))
      (node (ref "U1") (pin "96") (pinfunction "PC9_96") (pintype "bidirectional"))
    )
    (net (code "55") (name "USART1_RX") (class "Default")
      (node (ref "J18") (pin "13") (pinfunction "VCP_RX_13") (pintype "output"))
      (node (ref "U1") (pin "99") (pinfunction "PA10_99") (pintype "bidirectional"))
    )
    (net (code "56") (name "USART1_TX") (class "Default")
      (node (ref "J18") (pin "14") (pinfunction "VCP_TX_14") (pintype "input"))
      (node (ref "U1") (pin "98") (pinfunction "PA9_98") (pintype "bidirectional"))
    )
    (net (code "57") (name "USB_HS_DM") (class "Default")
      (node (ref "J17") (pin "2") (pinfunction "D_N_2") (pintype "bidirectional"))
      (node (ref "U1") (pin "74") (pinfunction "PB14_74") (pintype "bidirectional"))
    )
    (net (code "58") (name "USB_HS_DP") (class "Default")
      (node (ref "J17") (pin "3") (pinfunction "D_P_3") (pintype "bidirectional"))
      (node (ref "U1") (pin "75") (pinfunction "PB15_75") (pintype "bidirectional"))
    )
    (net (code "59") (name "X2_STOP") (class "Default")
      (node (ref "J1") (pin "2") (pinfunction "2_2") (pintype "passive"))
      (node (ref "U1") (pin "47") (pinfunction "PC4_47") (pintype "bidirectional"))
    )
    (net (code "60") (name "X_STOP") (class "Default")
      (node (ref "J1") (pin "1") (pinfunction "1_1") (pintype "passive"))
      (node (ref "U1") (pin "46") (pinfunction "PA7_46") (pintype "bidirectional"))
    )
    (net (code "61") (name "Y2_STOP") (class "Default")
      (node (ref "J1") (pin "4") (pinfunction "4_4") (pintype "passive"))
      (node (ref "U1") (pin "49") (pinfunction "PB0_49") (pintype "bidirectional"))
    )
    (net (code "62") (name "Y_STOP") (class "Default")
      (node (ref "J1") (pin "3") (pinfunction "3_3") (pintype "passive"))
      (node (ref "U1") (pin "48") (pinfunction "PC5_48") (pintype "bidirectional"))
    )
    (net (code "63") (name "Z2_STOP") (class "Default")
      (node (ref "J2") (pin "2") (pinfunction "2_2") (pintype "passive"))
      (node (ref "U1") (pin "51") (pinfunction "PB2_51") (pintype "bidirectional"))
    )
    (net (code "64") (name "Z_STOP") (class "Default")
      (node (ref "J2") (pin "1") (pinfunction "1_1") (pintype "passive"))
      (node (ref "U1") (pin "50") (pinfunction "PB1_50") (pintype "bidirectional"))
    )
    (net (code "65") (name "unconnected-(J17-ID-Pad4)") (class "Default")
      (node (ref "J17") (pin "4") (pinfunction "ID_4") (pintype "bidirectional"))
    )
    (net (code "66") (name "unconnected-(J18-GND_D-Pad12)") (class "Default")
      (node (ref "J18") (pin "12") (pinfunction "GND_D_12") (pintype "passive"))
    )
    (net (code "67") (name "unconnected-(J18-NC-Pad10)") (class "Default")
      (node (ref "J18") (pin "10") (pinfunction "NC_10") (pintype "passive"))
    )
    (net (code "68") (name "unconnected-(J18-RESV1-Pad1)") (class "Default")
      (node (ref "J18") (pin "1") (pinfunction "RESV1_1") (pintype "passive"))
    )
    (net (code "69") (name "unconnected-(J18-RESV2-Pad2)") (class "Default")
      (node (ref "J18") (pin "2") (pinfunction "RESV2_2") (pintype "passive"))
    )
    (net (code "70") (name "unconnected-(J18-RESV3-Pad9)") (class "Default")
      (node (ref "J18") (pin "9") (pinfunction "RESV3_9") (pintype "passive"))
    )
    (net (code "71") (name "unconnected-(J18-SWO-Pad8)") (class "Default")
      (node (ref "J18") (pin "8") (pinfunction "SWO_8") (pintype "passive"))
    )
    (net (code "72") (name "unconnected-(U1-PA6-Pad45)") (class "Default")
      (node (ref "U1") (pin "45") (pinfunction "PA6_45") (pintype "bidirectional"))
    )
    (net (code "73") (name "unconnected-(U1-PA8-Pad97)") (class "Default")
      (node (ref "U1") (pin "97") (pinfunction "PA8_97") (pintype "bidirectional"))
    )
    (net (code "74") (name "unconnected-(U1-PA11-Pad100)") (class "Default")
      (node (ref "U1") (pin "100") (pinfunction "PA11_100") (pintype "bidirectional"))
    )
    (net (code "75") (name "unconnected-(U1-PA12-Pad101)") (class "Default")
      (node (ref "U1") (pin "101") (pinfunction "PA12_101") (pintype "bidirectional"))
    )
    (net (code "76") (name "unconnected-(U1-PB3-Pad130)") (class "Default")
      (node (ref "U1") (pin "130") (pinfunction "PB3_130") (pintype "bidirectional"))
    )
    (net (code "77") (name "unconnected-(U1-PB4-Pad131)") (class "Default")
      (node (ref "U1") (pin "131") (pinfunction "PB4_131") (pintype "bidirectional"))
    )
    (net (code "78") (name "unconnected-(U1-PB5-Pad132)") (class "Default")
      (node (ref "U1") (pin "132") (pinfunction "PB5_132") (pintype "bidirectional"))
    )
    (net (code "79") (name "unconnected-(U1-PB6-Pad133)") (class "Default")
      (node (ref "U1") (pin "133") (pinfunction "PB6_133") (pintype "bidirectional"))
    )
    (net (code "80") (name "unconnected-(U1-PB7-Pad134)") (class "Default")
      (node (ref "U1") (pin "134") (pinfunction "PB7_134") (pintype "bidirectional"))
    )
    (net (code "81") (name "unconnected-(U1-PB8-Pad136)") (class "Default")
      (node (ref "U1") (pin "136") (pinfunction "PB8_136") (pintype "bidirectional"))
    )
    (net (code "82") (name "unconnected-(U1-PB9-Pad137)") (class "Default")
      (node (ref "U1") (pin "137") (pinfunction "PB9_137") (pintype "bidirectional"))
    )
    (net (code "83") (name "unconnected-(U1-PB10-Pad66)") (class "Default")
      (node (ref "U1") (pin "66") (pinfunction "PB10_66") (pintype "bidirectional"))
    )
    (net (code "84") (name "unconnected-(U1-PB11-Pad67)") (class "Default")
      (node (ref "U1") (pin "67") (pinfunction "PB11_67") (pintype "bidirectional"))
    )
    (net (code "85") (name "unconnected-(U1-PB12-Pad72)") (class "Default")
      (node (ref "U1") (pin "72") (pinfunction "PB12_72") (pintype "bidirectional"))
    )
    (net (code "86") (name "unconnected-(U1-PB13-Pad73)") (class "Default")
      (node (ref "U1") (pin "73") (pinfunction "PB13_73") (pintype "bidirectional"))
    )
    (net (code "87") (name "unconnected-(U1-PC10-Pad109)") (class "Default")
      (node (ref "U1") (pin "109") (pinfunction "PC10_109") (pintype "bidirectional"))
    )
    (net (code "88") (name "unconnected-(U1-PC11-Pad110)") (class "Default")
      (node (ref "U1") (pin "110") (pinfunction "PC11_110") (pintype "bidirectional"))
    )
    (net (code "89") (name "unconnected-(U1-PC12-Pad111)") (class "Default")
      (node (ref "U1") (pin "111") (pinfunction "PC12_111") (pintype "bidirectional"))
    )
    (net (code "90") (name "unconnected-(U1-PC13-Pad9)") (class "Default")
      (node (ref "U1") (pin "9") (pinfunction "PC13_9") (pintype "bidirectional"))
    )
    (net (code "91") (name "unconnected-(U1-PC14-Pad10)") (class "Default")
      (node (ref "U1") (pin "10") (pinfunction "PC14_10") (pintype "bidirectional"))
    )
    (net (code "92") (name "unconnected-(U1-PC15-Pad11)") (class "Default")
      (node (ref "U1") (pin "11") (pinfunction "PC15_11") (pintype "bidirectional"))
    )
    (net (code "93") (name "unconnected-(U1-PD0-Pad112)") (class "Default")
      (node (ref "U1") (pin "112") (pinfunction "PD0_112") (pintype "bidirectional"))
    )
    (net (code "94") (name "unconnected-(U1-PD1-Pad113)") (class "Default")
      (node (ref "U1") (pin "113") (pinfunction "PD1_113") (pintype "bidirectional"))
    )
    (net (code "95") (name "unconnected-(U1-PD2-Pad114)") (class "Default")
      (node (ref "U1") (pin "114") (pinfunction "PD2_114") (pintype "bidirectional"))
    )
    (net (code "96") (name "unconnected-(U1-PD3-Pad115)") (class "Default")
      (node (ref "U1") (pin "115") (pinfunction "PD3_115") (pintype "bidirectional"))
    )
    (net (code "97") (name "unconnected-(U1-PD4-Pad116)") (class "Default")
      (node (ref "U1") (pin "116") (pinfunction "PD4_116") (pintype "bidirectional"))
    )
    (net (code "98") (name "unconnected-(U1-PD5-Pad117)") (class "Default")
      (node (ref "U1") (pin "117") (pinfunction "PD5_117") (pintype "bidirectional"))
    )
    (net (code "99") (name "unconnected-(U1-PD6-Pad120)") (class "Default")
      (node (ref "U1") (pin "120") (pinfunction "PD6_120") (pintype "bidirectional"))
    )
    (net (code "100") (name "unconnected-(U1-PD7-Pad121)") (class "Default")
      (node (ref "U1") (pin "121") (pinfunction "PD7_121") (pintype "bidirectional"))
    )
    (net (code "101") (name "unconnected-(U1-PD8-Pad76)") (class "Default")
      (node (ref "U1") (pin "76") (pinfunction "PD8_76") (pintype "bidirectional"))
    )
    (net (code "102") (name "unconnected-(U1-PD9-Pad77)") (class "Default")
      (node (ref "U1") (pin "77") (pinfunction "PD9_77") (pintype "bidirectional"))
    )
    (net (code "103") (name "unconnected-(U1-PD10-Pad78)") (class "Default")
      (node (ref "U1") (pin "78") (pinfunction "PD10_78") (pintype "bidirectional"))
    )
    (net (code "104") (name "unconnected-(U1-PE0-Pad138)") (class "Default")
      (node (ref "U1") (pin "138") (pinfunction "PE0_138") (pintype "bidirectional"))
    )
    (net (code "105") (name "unconnected-(U1-PE1-Pad139)") (class "Default")
      (node (ref "U1") (pin "139") (pinfunction "PE1_139") (pintype "bidirectional"))
    )
    (net (code "106") (name "unconnected-(U1-PE6-Pad5)") (class "Default")
      (node (ref "U1") (pin "5") (pinfunction "PE6_5") (pintype "bidirectional"))
    )
    (net (code "107") (name "unconnected-(U1-PE7-Pad57)") (class "Default")
      (node (ref "U1") (pin "57") (pinfunction "PE7_57") (pintype "bidirectional"))
    )
    (net (code "108") (name "unconnected-(U1-PE8-Pad58)") (class "Default")
      (node (ref "U1") (pin "58") (pinfunction "PE8_58") (pintype "bidirectional"))
    )
    (net (code "109") (name "unconnected-(U1-PE10-Pad60)") (class "Default")
      (node (ref "U1") (pin "60") (pinfunction "PE10_60") (pintype "bidirectional"))
    )
    (net (code "110") (name "unconnected-(U1-PE12-Pad62)") (class "Default")
      (node (ref "U1") (pin "62") (pinfunction "PE12_62") (pintype "bidirectional"))
    )
    (net (code "111") (name "unconnected-(U1-PE15-Pad65)") (class "Default")
      (node (ref "U1") (pin "65") (pinfunction "PE15_65") (pintype "bidirectional"))
    )
    (net (code "112") (name "unconnected-(U1-PF10-Pad24)") (class "Default")
      (node (ref "U1") (pin "24") (pinfunction "PF10_24") (pintype "bidirectional"))
    )
    (net (code "113") (name "unconnected-(U1-PF11-Pad52)") (class "Default")
      (node (ref "U1") (pin "52") (pinfunction "PF11_52") (pintype "bidirectional"))
    )
    (net (code "114") (name "unconnected-(U1-PF14-Pad53)") (class "Default")
      (node (ref "U1") (pin "53") (pinfunction "PF14_53") (pintype "bidirectional"))
    )
    (net (code "115") (name "unconnected-(U1-PF15-Pad54)") (class "Default")
      (node (ref "U1") (pin "54") (pinfunction "PF15_54") (pintype "bidirectional"))
    )
    (net (code "116") (name "unconnected-(U1-PG7-Pad87)") (class "Default")
      (node (ref "U1") (pin "87") (pinfunction "PG7_87") (pintype "bidirectional"))
    )
    (net (code "117") (name "unconnected-(U1-PG8-Pad88)") (class "Default")
      (node (ref "U1") (pin "88") (pinfunction "PG8_88") (pintype "bidirectional"))
    )
    (net (code "118") (name "unconnected-(U1-PG9-Pad122)") (class "Default")
      (node (ref "U1") (pin "122") (pinfunction "PG9_122") (pintype "bidirectional"))
    )
    (net (code "119") (name "unconnected-(U1-PG10-Pad123)") (class "Default")
      (node (ref "U1") (pin "123") (pinfunction "PG10_123") (pintype "bidirectional"))
    )
    (net (code "120") (name "unconnected-(U1-PG11-Pad124)") (class "Default")
      (node (ref "U1") (pin "124") (pinfunction "PG11_124") (pintype "bidirectional"))
    )
    (net (code "121") (name "unconnected-(U1-PG12-Pad125)") (class "Default")
      (node (ref "U1") (pin "125") (pinfunction "PG12_125") (pintype "bidirectional"))
    )
    (net (code "122") (name "unconnected-(U1-PG13-Pad126)") (class "Default")
      (node (ref "U1") (pin "126") (pinfunction "PG13_126") (pintype "bidirectional"))
    )
    (net (code "123") (name "unconnected-(U1-PG14-Pad127)") (class "Default")
      (node (ref "U1") (pin "127") (pinfunction "PG14_127") (pintype "bidirectional"))
    )
    (net (code "124") (name "unconnected-(U1-PH0{slash}OSC_IN-Pad25)") (class "Default")
      (node (ref "U1") (pin "25") (pinfunction "PH0/OSC_IN_25") (pintype "bidirectional"))
    )
    (net (code "125") (name "unconnected-(U1-PH1{slash}OSC_OUT-Pad26)") (class "Default")
      (node (ref "U1") (pin "26") (pinfunction "PH1/OSC_OUT_26") (pintype "bidirectional"))
    )
    (net (code "126") (name "unconnected-(U1-VFBSMPS-Pad17)") (class "Default")
      (node (ref "U1") (pin "17") (pinfunction "VFBSMPS_17") (pintype "bidirectional"))
    )
    (net (code "127") (name "unconnected-(U1-VLXSMPS-Pad15)") (class "Default")
      (node (ref "U1") (pin "15") (pinfunction "VLXSMPS_15") (pintype "bidirectional"))
    )
    (net (code "128") (name "unconnected-(U2-BYP-Pad4)") (class "Default")
      (node (ref "U2") (pin "4") (pinfunction "BYP_4") (pintype "bidirectional"))
    )
  )
)
